# 4-PPS.net
KiCad netlist of a schematic drawn in Altium Designer
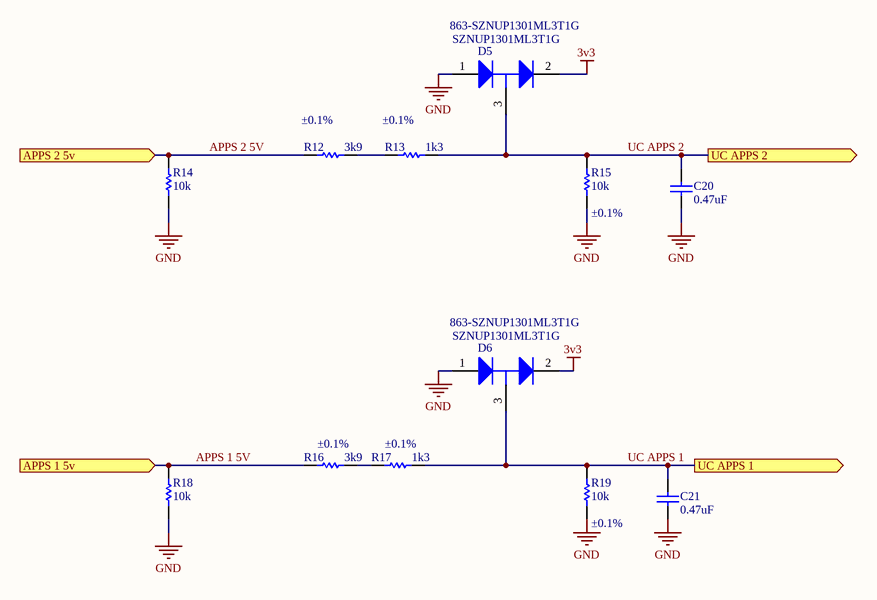
[diagram p0: 4-PPS.SchDoc]

(export (version "E")
  (design (tool "Eeschema 10.0.6"))
  (components
    (comp (ref "C20")
      (value "0.47uF")
      (footprint "1608[0603]")
      (description "Capacitor")
      (fields
        (field (name "MANUFACTURER") "Yageo")
        (field (name "MANUFACTURER PART NUMBER") "CC0603KRX7R8BB474")
      )
      (libsource (lib "Miscellaneous Devices") (part "Cap"))
    )
    (comp (ref "C21")
      (value "0.47uF")
      (footprint "1608[0603]")
      (description "Capacitor")
      (fields
        (field (name "MANUFACTURER") "Yageo")
        (field (name "MANUFACTURER PART NUMBER") "CC0603KRX7R8BB474")
      )
      (libsource (lib "Miscellaneous Devices") (part "Cap"))
    )
    (comp (ref "D5")
      (value "SZNUP1301ML3T1G")
      (footprint "ONSC-SOT-23-3-318-08_V")
      (fields
        (field (name "MANUFACTURER") "On Semiconductor")
        (field (name "SUPPLIER PART NUMBER 1") "863-SZNUP1301ML3T1G")
      )
      (libsource (lib "Altium Content Vault") (part "ONSC-NUP1301-SOT-23-3-318-08"))
    )
    (comp (ref "D6")
      (value "SZNUP1301ML3T1G")
      (footprint "ONSC-SOT-23-3-318-08_V")
      (fields
        (field (name "MANUFACTURER") "On Semiconductor")
        (field (name "SUPPLIER PART NUMBER 1") "863-SZNUP1301ML3T1G")
      )
      (libsource (lib "Altium Content Vault") (part "ONSC-NUP1301-SOT-23-3-318-08"))
    )
    (comp (ref "R12")
      (value "3k9")
      (footprint "1608[0603]")
      (description "Resistor")
      (fields
        (field (name "MANUFACTURER") "Yageo")
        (field (name "MANUFACTURER PART NUMBER") "RT0603BRD073K9L")
        (field (name "TOLERANCE") "±0.1%")
      )
      (libsource (lib "Miscellaneous Devices") (part "Res1"))
    )
    (comp (ref "R13")
      (value "1k3")
      (footprint "1608[0603]")
      (description "Resistor")
      (fields
        (field (name "MANUFACTURER") "Yageo")
        (field (name "MANUFACTURER PART NUMBER") "RT0603BRD071K3L")
        (field (name "TOLERANCE") "±0.1%")
      )
      (libsource (lib "Miscellaneous Devices") (part "Res1"))
    )
    (comp (ref "R14")
      (value "10k")
      (footprint "1608[0603]")
      (description "Resistor")
      (fields
        (field (name "MANUFACTURER") "Yageo")
        (field (name "MANUFACTURER PART NUMBER") "RC0603JR-0710KL")
      )
      (libsource (lib "Miscellaneous Devices") (part "Res1"))
    )
    (comp (ref "R15")
      (value "10k")
      (footprint "1608[0603]")
      (description "Resistor")
      (fields
        (field (name "MANUFACTURER") "Yageo")
        (field (name "MANUFACTURER PART NUMBER") "RT0603BRD0710KL")
        (field (name "TOLERANCE") "±0.1%")
      )
      (libsource (lib "Miscellaneous Devices") (part "Res1"))
    )
    (comp (ref "R16")
      (value "3k9")
      (footprint "1608[0603]")
      (description "Resistor")
      (fields
        (field (name "MANUFACTURER") "Yageo")
        (field (name "MANUFACTURER PART NUMBER") "RT0603BRD073K9L")
        (field (name "TOLERANCE") "±0.1%")
      )
      (libsource (lib "Miscellaneous Devices") (part "Res1"))
    )
    (comp (ref "R17")
      (value "1k3")
      (footprint "1608[0603]")
      (description "Resistor")
      (fields
        (field (name "MANUFACTURER") "Yageo")
        (field (name "MANUFACTURER PART NUMBER") "RT0603BRD071K3L")
        (field (name "TOLERANCE") "±0.1%")
      )
      (libsource (lib "Miscellaneous Devices") (part "Res1"))
    )
    (comp (ref "R18")
      (value "10k")
      (footprint "1608[0603]")
      (description "Resistor")
      (fields
        (field (name "MANUFACTURER") "Yageo")
        (field (name "MANUFACTURER PART NUMBER") "RC0603JR-0710KL")
      )
      (libsource (lib "Miscellaneous Devices") (part "Res1"))
    )
    (comp (ref "R19")
      (value "10k")
      (footprint "1608[0603]")
      (description "Resistor")
      (fields
        (field (name "MANUFACTURER") "Yageo")
        (field (name "MANUFACTURER PART NUMBER") "RT0603BRD0710KL")
        (field (name "TOLERANCE") "±0.1%")
      )
      (libsource (lib "Miscellaneous Devices") (part "Res1"))
    )
  )
  (nets
    (net (code "1") (name "/APPS 1 5V") (class "Default")
      (node (ref "R16") (pin "1") (pinfunction "1_1") (pintype "passive"))
      (node (ref "R18") (pin "2") (pinfunction "2_2") (pintype "passive"))
    )
    (net (code "2") (name "/APPS 2 5V") (class "Default")
      (node (ref "R12") (pin "1") (pinfunction "1_1") (pintype "passive"))
      (node (ref "R14") (pin "2") (pinfunction "2_2") (pintype "passive"))
    )
    (net (code "3") (name "/UC APPS 1") (class "Default")
      (node (ref "C21") (pin "2") (pinfunction "2_2") (pintype "passive"))
      (node (ref "D6") (pin "3") (pinfunction "K/A_3") (pintype "passive"))
      (node (ref "R17") (pin "2") (pinfunction "2_2") (pintype "passive"))
      (node (ref "R19") (pin "2") (pinfunction "2_2") (pintype "passive"))
    )
    (net (code "4") (name "/UC APPS 2") (class "Default")
      (node (ref "C20") (pin "2") (pinfunction "2_2") (pintype "passive"))
      (node (ref "D5") (pin "3") (pinfunction "K/A_3") (pintype "passive"))
      (node (ref "R13") (pin "2") (pinfunction "2_2") (pintype "passive"))
      (node (ref "R15") (pin "2") (pinfunction "2_2") (pintype "passive"))
    )
    (net (code "5") (name "3v3") (class "Default")
      (node (ref "D5") (pin "2") (pinfunction "K_2") (pintype "passive"))
      (node (ref "D6") (pin "2") (pinfunction "K_2") (pintype "passive"))
    )
    (net (code "6") (name "GND") (class "Default")
      (node (ref "C20") (pin "1") (pinfunction "1_1") (pintype "passive"))
      (node (ref "C21") (pin "1") (pinfunction "1_1") (pintype "passive"))
      (node (ref "D5") (pin "1") (pinfunction "A_1") (pintype "passive"))
      (node (ref "D6") (pin "1") (pinfunction "A_1") (pintype "passive"))
      (node (ref "R14") (pin "1") (pinfunction "1_1") (pintype "passive"))
      (node (ref "R15") (pin "1") (pinfunction "1_1") (pintype "passive"))
      (node (ref "R18") (pin "1") (pinfunction "1_1") (pintype "passive"))
      (node (ref "R19") (pin "1") (pinfunction "1_1") (pintype "passive"))
    )
    (net (code "7") (name "Net-(R12-Pad2)") (class "Default")
      (node (ref "R12") (pin "2") (pinfunction "2_2") (pintype "passive"))
      (node (ref "R13") (pin "1") (pinfunction "1_1") (pintype "passive"))
    )
    (net (code "8") (name "Net-(R16-Pad2)") (class "Default")
      (node (ref "R16") (pin "2") (pinfunction "2_2") (pintype "passive"))
      (node (ref "R17") (pin "1") (pinfunction "1_1") (pintype "passive"))
    )
  )
)
